# Horloge_Oscillator.net
KiCad netlist of a schematic drawn in Altium Designer
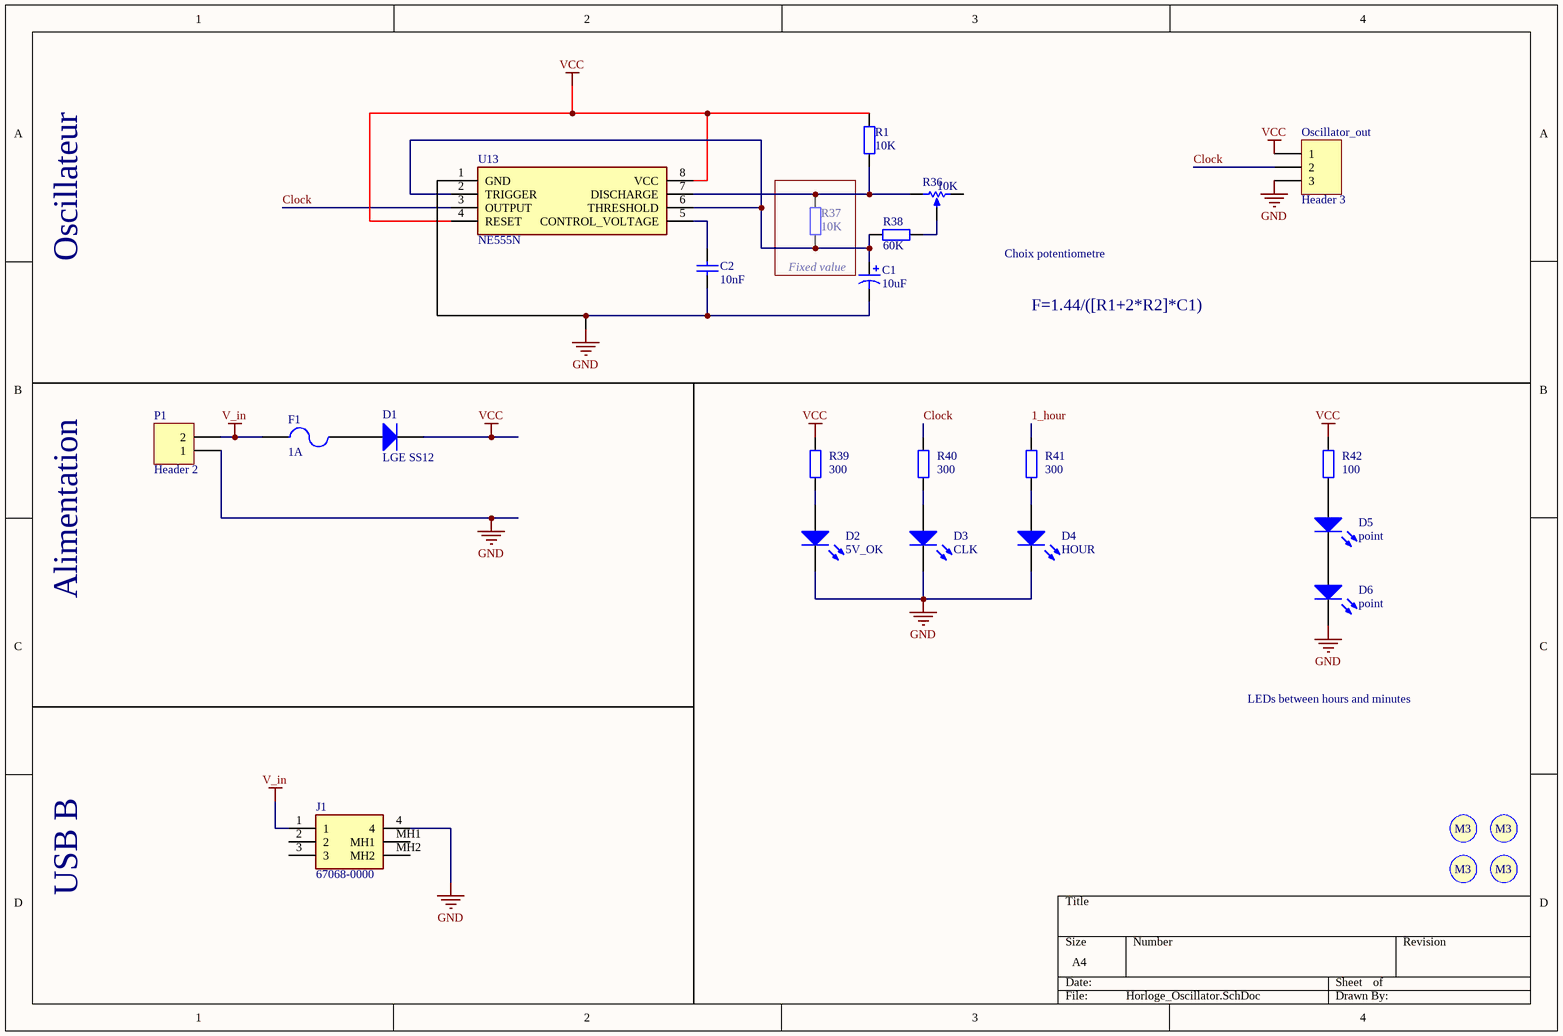
[diagram p0: Horloge_Oscillator.SchDoc]

(export (version "E")
  (design (tool "Eeschema 10.0.6"))
  (components
    (comp (ref "C1")
      (value "10uF")
      (footprint "Capacitor 1206")
      (description "Polarized Capacitor (Radial)")
      (fields (field (name "Comment") "Cap Pol1") (field (name "PUBLISHER") "Altium Limited"))
      (libsource (lib "Miscellaneous Devices") (part "Cap Pol1"))
    )
    (comp (ref "C2")
      (value "10nF")
      (footprint "Capacitor 1206")
      (description "Capacitor")
      (fields (field (name "Comment") "Cap") (field (name "PUBLISHER") "Altium Limited"))
      (libsource (lib "Miscellaneous Devices") (part "Cap"))
    )
    (comp (ref "D1")
      (value "LGE SS12")
      (footprint "SMB")
      (description "Default Diode")
      (fields (field (name "PUBLISHER") "Altium Limited"))
      (libsource (lib "Miscellaneous Devices") (part "Diode"))
    )
    (comp (ref "D2")
      (value "5V_OK")
      (footprint "KP-3216SEC")
      (description "Typical RED, GREEN, YELLOW, AMBER GaAs LED")
      (fields (field (name "PUBLISHER") "Altium Limited"))
      (libsource (lib "Miscellaneous Devices") (part "LED2"))
    )
    (comp (ref "D3")
      (value "CLK")
      (footprint "KP-3216SEC")
      (description "Typical RED, GREEN, YELLOW, AMBER GaAs LED")
      (fields (field (name "PUBLISHER") "Altium Limited"))
      (libsource (lib "Miscellaneous Devices") (part "LED2"))
    )
    (comp (ref "D4")
      (value "HOUR")
      (footprint "KP-3216SEC")
      (description "Typical RED, GREEN, YELLOW, AMBER GaAs LED")
      (fields (field (name "PUBLISHER") "Altium Limited"))
      (libsource (lib "Miscellaneous Devices") (part "LED2"))
    )
    (comp (ref "D5")
      (value "point")
      (footprint "KP-3216SEC")
      (description "Typical RED, GREEN, YELLOW, AMBER GaAs LED")
      (fields (field (name "PUBLISHER") "Altium Limited"))
      (libsource (lib "Miscellaneous Devices") (part "LED2"))
    )
    (comp (ref "D6")
      (value "point")
      (footprint "KP-3216SEC")
      (description "Typical RED, GREEN, YELLOW, AMBER GaAs LED")
      (fields (field (name "PUBLISHER") "Altium Limited"))
      (libsource (lib "Miscellaneous Devices") (part "LED2"))
    )
    (comp (ref "F1")
      (value "1A")
      (footprint "3.5X2.8X1.9")
      (description "Fuse")
      (fields (field (name "PUBLISHER") "Altium Limited"))
      (libsource (lib "Miscellaneous Devices") (part "Fuse 2"))
    )
    (comp (ref "J1")
      (value "67068-0000")
      (footprint "670680000")
      (description "Connector")
      (fields (field (name "MOUSER PART NUMBER") "538-67068-0000"))
      (libsource (lib "*") (part "67068-0000"))
    )
    (comp (ref "Oscillator_out")
      (value "Header 3")
      (footprint "HDR1X3")
      (description "Header, 3-Pin")
      (fields (field (name "PUBLISHER") "Altium Limited"))
      (libsource (lib "Miscellaneous Connectors") (part "Header 3"))
    )
    (comp (ref "P1")
      (value "Header 2")
      (footprint "HDR1X2")
      (description "Header, 2-Pin")
      (fields (field (name "PUBLISHER") "Altium Limited"))
      (libsource (lib "Miscellaneous Connectors") (part "Header 2"))
    )
    (comp (ref "R1")
      (value "10K")
      (footprint "Resistor 1206")
      (description "Resistor")
      (fields (field (name "Comment") "Res2") (field (name "PUBLISHER") "Altium Limited"))
      (libsource (lib "") (part "Res2_1"))
    )
    (comp (ref "R36")
      (value "10K")
      (footprint "EVMAASA00B15")
      (description "Potentiometer")
      (fields (field (name "Comment") "RPot") (field (name "PUBLISHER") "Altium Limited"))
      (libsource (lib "Miscellaneous Devices") (part "RPot"))
    )
    (comp (ref "R37")
      (value "10K")
      (footprint "Resistor 1206")
      (description "Resistor")
      (fields (field (name "Comment") "Res2") (field (name "PUBLISHER") "Altium Limited"))
      (libsource (lib "Miscellaneous Devices") (part "Res2"))
    )
    (comp (ref "R38")
      (value "60K")
      (footprint "Resistor 1206")
      (description "Resistor")
      (fields (field (name "Comment") "Res2") (field (name "PUBLISHER") "Altium Limited"))
      (libsource (lib "") (part "Res2_2"))
    )
    (comp (ref "R39")
      (value "300")
      (footprint "Resistor 1206")
      (description "Resistor")
      (fields (field (name "Comment") "Res2") (field (name "PUBLISHER") "Altium Limited"))
      (libsource (lib "Miscellaneous Devices") (part "Res2"))
    )
    (comp (ref "R40")
      (value "300")
      (footprint "Resistor 1206")
      (description "Resistor")
      (fields (field (name "Comment") "Res2") (field (name "PUBLISHER") "Altium Limited"))
      (libsource (lib "Miscellaneous Devices") (part "Res2"))
    )
    (comp (ref "R41")
      (value "300")
      (footprint "Resistor 1206")
      (description "Resistor")
      (fields (field (name "Comment") "Res2") (field (name "PUBLISHER") "Altium Limited"))
      (libsource (lib "Miscellaneous Devices") (part "Res2"))
    )
    (comp (ref "R42")
      (value "100")
      (footprint "Resistor 1206")
      (description "Resistor")
      (fields (field (name "Comment") "Res2") (field (name "PUBLISHER") "Altium Limited"))
      (libsource (lib "Miscellaneous Devices") (part "Res2"))
    )
    (comp (ref "S0")
      (value "Screw M3")
      (footprint "Screw M3")
      (libsource (lib "Robot_2020") (part "Screw M3"))
    )
    (comp (ref "S3")
      (value "Screw M3")
      (footprint "Screw M3")
      (libsource (lib "Robot_2020") (part "Screw M3"))
    )
    (comp (ref "U13")
      (value "NE555N")
      (footprint "DIP762W56P254L959H533Q8N")
      (description "Integrated Circuit")
      (libsource (lib "*") (part "NE555N"))
    )
  )
  (nets
    (net (code "1") (name "/1_hour") (class "Default")
      (node (ref "R41") (pin "2") (pinfunction "2_2") (pintype "passive"))
    )
    (net (code "2") (name "/Clock") (class "Default")
      (node (ref "Oscillator_out") (pin "2") (pinfunction "2_2") (pintype "passive"))
      (node (ref "R40") (pin "2") (pinfunction "2_2") (pintype "passive"))
      (node (ref "U13") (pin "3") (pinfunction "OUTPUT_3") (pintype "passive"))
    )
    (net (code "3") (name "GND") (class "Default")
      (node (ref "C1") (pin "2") (pinfunction "2_2") (pintype "passive"))
      (node (ref "C2") (pin "1") (pinfunction "1_1") (pintype "passive"))
      (node (ref "D2") (pin "2") (pinfunction "K_2") (pintype "passive"))
      (node (ref "D3") (pin "2") (pinfunction "K_2") (pintype "passive"))
      (node (ref "D4") (pin "2") (pinfunction "K_2") (pintype "passive"))
      (node (ref "D6") (pin "2") (pinfunction "K_2") (pintype "passive"))
      (node (ref "J1") (pin "4") (pinfunction "4_4") (pintype "passive"))
      (node (ref "Oscillator_out") (pin "3") (pinfunction "3_3") (pintype "passive"))
      (node (ref "P1") (pin "1") (pinfunction "1_1") (pintype "passive"))
      (node (ref "U13") (pin "1") (pinfunction "GND_1") (pintype "passive"))
    )
    (net (code "4") (name "Net-(D1-A)") (class "Default")
      (node (ref "D1") (pin "1") (pinfunction "A_1") (pintype "passive"))
      (node (ref "F1") (pin "1") (pinfunction "1_1") (pintype "passive"))
    )
    (net (code "5") (name "Net-(D2-A)") (class "Default")
      (node (ref "D2") (pin "1") (pinfunction "A_1") (pintype "passive"))
      (node (ref "R39") (pin "1") (pinfunction "1_1") (pintype "passive"))
    )
    (net (code "6") (name "Net-(D3-A)") (class "Default")
      (node (ref "D3") (pin "1") (pinfunction "A_1") (pintype "passive"))
      (node (ref "R40") (pin "1") (pinfunction "1_1") (pintype "passive"))
    )
    (net (code "7") (name "Net-(D4-A)") (class "Default")
      (node (ref "D4") (pin "1") (pinfunction "A_1") (pintype "passive"))
      (node (ref "R41") (pin "1") (pinfunction "1_1") (pintype "passive"))
    )
    (net (code "8") (name "Net-(D5-A)") (class "Default")
      (node (ref "D5") (pin "1") (pinfunction "A_1") (pintype "passive"))
      (node (ref "R42") (pin "1") (pinfunction "1_1") (pintype "passive"))
    )
    (net (code "9") (name "Net-(D5-K)") (class "Default")
      (node (ref "D5") (pin "2") (pinfunction "K_2") (pintype "passive"))
      (node (ref "D6") (pin "1") (pinfunction "A_1") (pintype "passive"))
    )
    (net (code "10") (name "Net-(R36-TAP)") (class "Default")
      (node (ref "R36") (pin "3") (pinfunction "TAP_3") (pintype "passive"))
      (node (ref "R38") (pin "1") (pinfunction "1_1") (pintype "passive"))
    )
    (net (code "11") (name "Net-(R36-TOP)") (class "Default")
      (node (ref "R1") (pin "2") (pinfunction "2_2") (pintype "passive"))
      (node (ref "R36") (pin "1") (pinfunction "TOP_1") (pintype "passive"))
      (node (ref "R37") (pin "2") (pinfunction "2_2") (pintype "passive"))
      (node (ref "U13") (pin "7") (pinfunction "DISCHARGE_7") (pintype "passive"))
    )
    (net (code "12") (name "Net-(U13-CONTROL_VOLTAGE)") (class "Default")
      (node (ref "C2") (pin "2") (pinfunction "2_2") (pintype "passive"))
      (node (ref "U13") (pin "5") (pinfunction "CONTROL_VOLTAGE_5") (pintype "passive"))
    )
    (net (code "13") (name "Net-(U13-THRESHOLD)") (class "Default")
      (node (ref "C1") (pin "1") (pinfunction "1_1") (pintype "passive"))
      (node (ref "R37") (pin "1") (pinfunction "1_1") (pintype "passive"))
      (node (ref "R38") (pin "2") (pinfunction "2_2") (pintype "passive"))
      (node (ref "U13") (pin "2") (pinfunction "TRIGGER_2") (pintype "passive"))
      (node (ref "U13") (pin "6") (pinfunction "THRESHOLD_6") (pintype "passive"))
    )
    (net (code "14") (name "VCC") (class "Default")
      (node (ref "D1") (pin "2") (pinfunction "K_2") (pintype "passive"))
      (node (ref "Oscillator_out") (pin "1") (pinfunction "1_1") (pintype "passive"))
      (node (ref "R1") (pin "1") (pinfunction "1_1") (pintype "passive"))
      (node (ref "R39") (pin "2") (pinfunction "2_2") (pintype "passive"))
      (node (ref "R42") (pin "2") (pinfunction "2_2") (pintype "passive"))
      (node (ref "U13") (pin "4") (pinfunction "RESET_4") (pintype "passive"))
      (node (ref "U13") (pin "8") (pinfunction "VCC_8") (pintype "passive"))
    )
    (net (code "15") (name "V_in") (class "Default")
      (node (ref "F1") (pin "2") (pinfunction "2_2") (pintype "passive"))
      (node (ref "J1") (pin "1") (pinfunction "1_1") (pintype "passive"))
      (node (ref "P1") (pin "2") (pinfunction "2_2") (pintype "passive"))
    )
    (net (code "16") (name "unconnected-(J1-Pad2)") (class "Default")
      (node (ref "J1") (pin "2") (pinfunction "2_2") (pintype "passive"))
    )
    (net (code "17") (name "unconnected-(J1-Pad3)") (class "Default")
      (node (ref "J1") (pin "3") (pinfunction "3_3") (pintype "passive"))
    )
    (net (code "18") (name "unconnected-(J1-PadMH1)") (class "Default")
      (node (ref "J1") (pin "MH1") (pinfunction "MH1_MH1") (pintype "passive"))
    )
    (net (code "19") (name "unconnected-(J1-PadMH2)") (class "Default")
      (node (ref "J1") (pin "MH2") (pinfunction "MH2_MH2") (pintype "passive"))
    )
    (net (code "20") (name "unconnected-(R36-BOT-Pad2)") (class "Default")
      (node (ref "R36") (pin "2") (pinfunction "BOT_2") (pintype "passive"))
    )
  )
)
